# Sheet86.net
KiCad netlist of a schematic drawn in Altium Designer
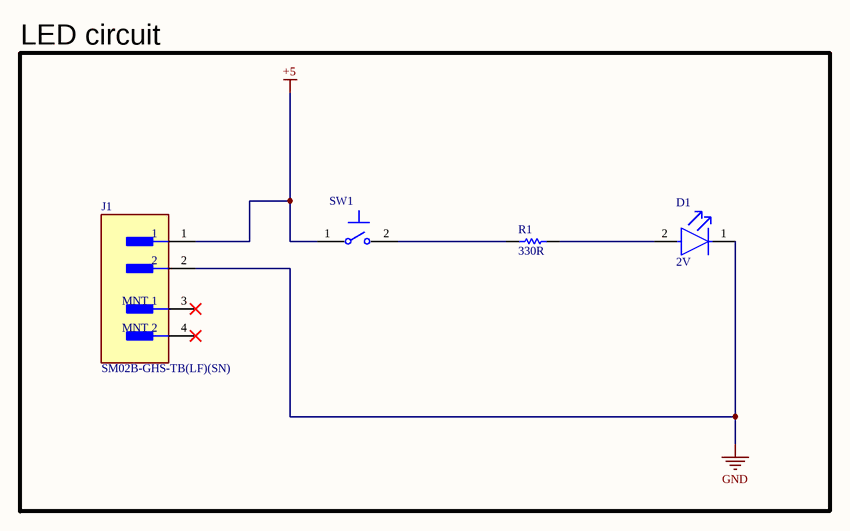
[diagram p0: Sheet86.SchDoc]

(export (version "E")
  (design (tool "Eeschema 10.0.6"))
  (components
    (comp (ref "D1")
      (value "2V")
      (footprint "FP-LTST-C190GKT-MFG")
      (description "LED GREEN CLEAR CHIP SMD")
      (libsource (lib "Altium Content Vault") (part "8706943c75ba83719d021d2fdc84c58"))
    )
    (comp (ref "J1")
      (value "SM02B-GHS-TB(LF)(SN)")
      (footprint "FP-SM02B-GHS-TB_LF_SN-MFG")
      (description "CONN HEADER SMD R/A 2POS 1.25MM")
      (libsource (lib "Altium Content Vault") (part "56ec3178a87b3978bdc1b3682cd516a"))
    )
    (comp (ref "R1")
      (value "330R")
      (footprint "RESC1608X55X25NL10T15")
      (description "Chip Resistor, 330 Ohm, +/- 1%, 0.1 W, -55 to 155 degC, 0603 (1608 Metric), RoHS, Tape and Reel")
      (fields (field (name "TOLERANCE") "10%"))
      (libsource (lib "Altium Content Vault") (part "RES-2"))
    )
    (comp (ref "SW1")
      (value "~")
      (footprint "FP-TL1015AF160QG-MFG")
      (description "SWITCH TACTILE SPST-NO 0.05A 12V")
      (libsource (lib "Altium Content Vault") (part "2041f8efb62e6aaa548c9fd35e2c2f1"))
    )
  )
  (nets
    (net (code "1") (name "+5") (class "Default")
      (node (ref "J1") (pin "1") (pinfunction "1_1") (pintype "passive"))
      (node (ref "SW1") (pin "1") (pinfunction "1_1") (pintype "passive"))
    )
    (net (code "2") (name "GND") (class "Default")
      (node (ref "D1") (pin "1") (pinfunction "C_1") (pintype "passive"))
      (node (ref "J1") (pin "2") (pinfunction "2_2") (pintype "passive"))
    )
    (net (code "3") (name "Net-(D1-A)") (class "Default")
      (node (ref "D1") (pin "2") (pinfunction "A_2") (pintype "passive"))
      (node (ref "R1") (pin "2") (pinfunction "2_2") (pintype "passive"))
    )
    (net (code "4") (name "Net-(R1-Pad1)") (class "Default")
      (node (ref "R1") (pin "1") (pinfunction "1_1") (pintype "passive"))
      (node (ref "SW1") (pin "2") (pinfunction "2_2") (pintype "passive"))
    )
    (net (code "5") (name "unconnected-(J1-MNT_1-Pad3)") (class "Default")
      (node (ref "J1") (pin "3") (pinfunction "MNT_1_3") (pintype "passive+no_connect"))
    )
    (net (code "6") (name "unconnected-(J1-MNT_2-Pad4)") (class "Default")
      (node (ref "J1") (pin "4") (pinfunction "MNT_2_4") (pintype "passive+no_connect"))
    )
  )
)
